# MCU.net
KiCad netlist of a schematic drawn in Altium Designer
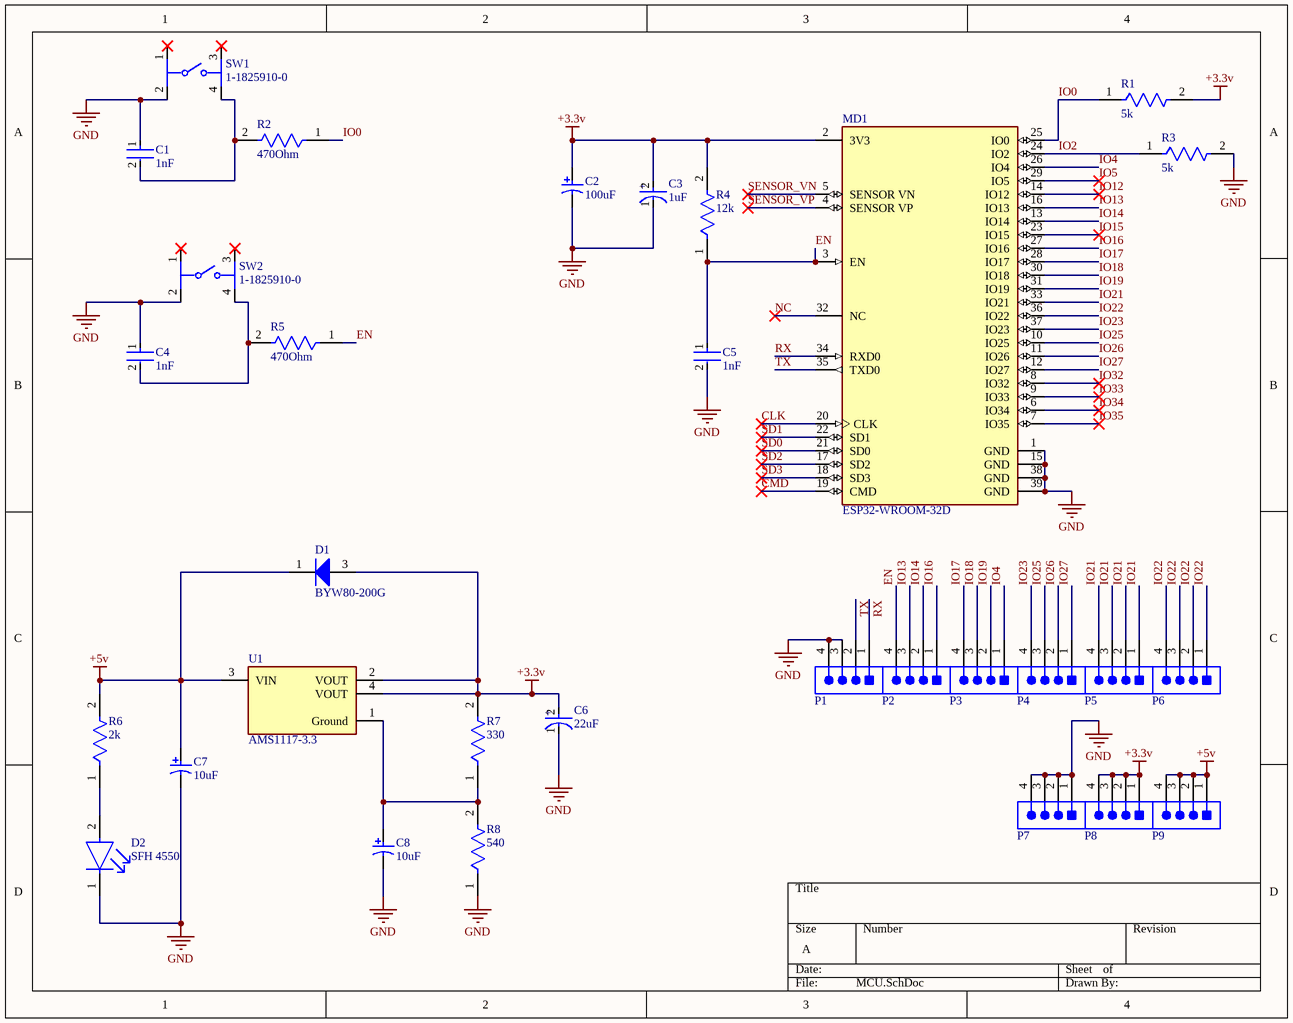
[diagram p0: MCU.SchDoc]

(export (version "E")
  (design (tool "Eeschema 10.0.6"))
  (components
    (comp (ref "C1")
      (value "1nF")
      (footprint "FP-VY2102M29Y5US6TV7-MFG")
      (fields (field (name "VOLTAGE") "300V") (field (name "TOLERANCE") "20%"))
      (libsource (lib "Altium Content Vault") (part "11868f565c42a9108669ba33697ecf6"))
    )
    (comp (ref "C2")
      (value "100uF")
      (footprint "NIC-RNS-8x11.5-2_V")
      (description "Aluminum Electrolytic Capacitor, 100 uF +/-20%, 10 V, -55 to 105 degC, 2-Pin THD, RoHS")
      (fields (field (name "PARTNUMBER") "RNS1A101MDN1KX") (field (name "MANUFACTURER") "Nichicon"))
      (libsource (lib "Altium Content Vault") (part "NIC-CAP-P-2"))
    )
    (comp (ref "C3")
      (value "1uF")
      (footprint "FP-ECA-2WHG010-MFG")
      (description "ECA-2WHG010 Aluminum Electrolytic Capacitor, 1 uF, 450 V, ± 20%, 2000 hours @ 105°C, Radial Leaded")
      (fields (field (name "TOLERANCE") "20%") (field (name "VOLTAGE") "450V"))
      (libsource (lib "Altium Content Vault") (part "a00bbbee19879c290e62620ae7e47b1"))
    )
    (comp (ref "C4")
      (value "1nF")
      (footprint "FP-VY2102M29Y5US6TV7-MFG")
      (fields (field (name "VOLTAGE") "300V") (field (name "TOLERANCE") "20%"))
      (libsource (lib "Altium Content Vault") (part "11868f565c42a9108669ba33697ecf6"))
    )
    (comp (ref "C5")
      (value "1nF")
      (footprint "FP-VY2102M29Y5US6TV7-MFG")
      (fields (field (name "VOLTAGE") "300V") (field (name "TOLERANCE") "20%"))
      (libsource (lib "Altium Content Vault") (part "11868f565c42a9108669ba33697ecf6"))
    )
    (comp (ref "C6")
      (value "22uF")
      (footprint "FP-RAD-TH-D_16_0_5-L_20_2-MFG")
      (description "Aluminum Electrolytic Capacitors (Radial Lead Type) 22uF ±20% 450V")
      (fields (field (name "TOLERANCE") "20%") (field (name "VOLTAGE") "450V"))
      (libsource (lib "Altium Content Vault") (part "203bc49f2ac43e59fd269a8c329ed05"))
    )
    (comp (ref "C7")
      (value "10uF")
      (footprint "NIC-RNS-8x11.5-2_V")
      (description "Aluminum Electrolytic Capacitor, 100 uF +/-20%, 10 V, -55 to 105 degC, 2-Pin THD, RoHS")
      (fields (field (name "PARTNUMBER") "RNS1A101MDN1KX") (field (name "MANUFACTURER") "Nichicon"))
      (libsource (lib "Altium Content Vault") (part "NIC-CAP-P-2"))
    )
    (comp (ref "C8")
      (value "10uF")
      (footprint "NIC-RNS-8x11.5-2_V")
      (description "Aluminum Electrolytic Capacitor, 100 uF +/-20%, 10 V, -55 to 105 degC, 2-Pin THD, RoHS")
      (fields (field (name "PARTNUMBER") "RNS1A101MDN1KX") (field (name "MANUFACTURER") "Nichicon"))
      (libsource (lib "Altium Content Vault") (part "NIC-CAP-P-2"))
    )
    (comp (ref "D1")
      (value "BYW80-200G")
      (footprint "ONSC-TO-220-2-221B-04_E")
      (description "SWITCHMODE(TM) Power Rectifier, 2-Pin TO-220, Pb-Free, Tube")
      (fields (field (name "MANUFACTURER") "On Semiconductor"))
      (libsource (lib "Altium Content Vault") (part "ONSC-D-K1A3-2_A"))
    )
    (comp (ref "D2")
      (value "SFH 4550")
      (footprint "FP-SFH_4550-MFG")
      (description "EMITTER IR 860NM 100MA RADIAL")
      (fields
        (field (name "OCTOPART") "https://octopart.com/sfh+4550-osram+opto-55410894")
        (field (name "MANUFACTURER") "Osram Opto")
      )
      (libsource (lib "Altium Content Vault") (part "75a0115997dd6a71327e26aab64f6f8"))
    )
    (comp (ref "MD1")
      (value "ESP32-WROOM-32D")
      (footprint "FP-ESP32-WROOM-32D-MFG")
      (description "WIFI MODULE 32MBITS SPI FLASH")
      (fields
        (field (name "OCTOPART") "https://octopart.com/esp32-wroom-32d-espressif+systems-91040050")
        (field (name "MANUFACTURER") "Espressif Systems")
      )
      (libsource (lib "Altium Content Vault") (part "a031a76f8c27026a7a7f4657ff233a3"))
    )
    (comp (ref "P1")
      (value "B4B-EH-A(LF)(SN)")
      (footprint "JST-B4B-EH-A_V")
      (fields (field (name "MANUFACTURER") "JST"))
      (libsource (lib "Altium Content Vault") (part "CN-1P-M-R4"))
    )
    (comp (ref "P2")
      (value "B4B-EH-A(LF)(SN)")
      (footprint "JST-B4B-EH-A_V")
      (fields (field (name "MANUFACTURER") "JST"))
      (libsource (lib "Altium Content Vault") (part "CN-1P-M-R4"))
    )
    (comp (ref "P3")
      (value "B4B-EH-A(LF)(SN)")
      (footprint "JST-B4B-EH-A_V")
      (fields (field (name "MANUFACTURER") "JST"))
      (libsource (lib "Altium Content Vault") (part "CN-1P-M-R4"))
    )
    (comp (ref "P4")
      (value "B4B-EH-A(LF)(SN)")
      (footprint "JST-B4B-EH-A_V")
      (fields (field (name "MANUFACTURER") "JST"))
      (libsource (lib "Altium Content Vault") (part "CN-1P-M-R4"))
    )
    (comp (ref "P5")
      (value "B4B-EH-A(LF)(SN)")
      (footprint "JST-B4B-EH-A_V")
      (fields (field (name "MANUFACTURER") "JST"))
      (libsource (lib "Altium Content Vault") (part "CN-1P-M-R4"))
    )
    (comp (ref "P6")
      (value "B4B-EH-A(LF)(SN)")
      (footprint "JST-B4B-EH-A_V")
      (fields (field (name "MANUFACTURER") "JST"))
      (libsource (lib "Altium Content Vault") (part "CN-1P-M-R4"))
    )
    (comp (ref "P7")
      (value "B4B-EH-A(LF)(SN)")
      (footprint "JST-B4B-EH-A_V")
      (fields (field (name "MANUFACTURER") "JST"))
      (libsource (lib "Altium Content Vault") (part "CN-1P-M-R4"))
    )
    (comp (ref "P8")
      (value "B4B-EH-A(LF)(SN)")
      (footprint "JST-B4B-EH-A_V")
      (fields (field (name "MANUFACTURER") "JST"))
      (libsource (lib "Altium Content Vault") (part "CN-1P-M-R4"))
    )
    (comp (ref "P9")
      (value "B4B-EH-A(LF)(SN)")
      (footprint "JST-B4B-EH-A_V")
      (fields (field (name "MANUFACTURER") "JST"))
      (libsource (lib "Altium Content Vault") (part "CN-1P-M-R4"))
    )
    (comp (ref "R1")
      (value "5k")
      (footprint "FP-MRS1600-MFG")
      (description "RES 20K OHM 0.4W 1% AXIAL")
      (fields (field (name "TOLERANCE") "1%"))
      (libsource (lib "Altium Content Vault") (part "1029c3af85768c4190bb7ad29bc67b5"))
    )
    (comp (ref "R2")
      (value "470Ohm")
      (footprint "FP-MRS1600-MFG")
      (description "RES 20K OHM 0.4W 1% AXIAL")
      (fields (field (name "TOLERANCE") "1%"))
      (libsource (lib "Altium Content Vault") (part "1029c3af85768c4190bb7ad29bc67b5"))
    )
    (comp (ref "R3")
      (value "5k")
      (footprint "FP-MRS1600-MFG")
      (description "RES 20K OHM 0.4W 1% AXIAL")
      (fields (field (name "TOLERANCE") "1%"))
      (libsource (lib "Altium Content Vault") (part "1029c3af85768c4190bb7ad29bc67b5"))
    )
    (comp (ref "R4")
      (value "12k")
      (footprint "FP-MRS1600-MFG")
      (description "RES 20K OHM 0.4W 1% AXIAL")
      (fields (field (name "TOLERANCE") "1%"))
      (libsource (lib "Altium Content Vault") (part "1029c3af85768c4190bb7ad29bc67b5"))
    )
    (comp (ref "R5")
      (value "470Ohm")
      (footprint "FP-MRS1600-MFG")
      (description "RES 20K OHM 0.4W 1% AXIAL")
      (fields (field (name "TOLERANCE") "1%"))
      (libsource (lib "Altium Content Vault") (part "1029c3af85768c4190bb7ad29bc67b5"))
    )
    (comp (ref "R6")
      (value "2k")
      (footprint "FP-MRS1600-MFG")
      (description "RES 20K OHM 0.4W 1% AXIAL")
      (fields (field (name "TOLERANCE") "1%"))
      (libsource (lib "Altium Content Vault") (part "1029c3af85768c4190bb7ad29bc67b5"))
    )
    (comp (ref "R7")
      (value "330")
      (footprint "FP-MRS1600-MFG")
      (description "RES 20K OHM 0.4W 1% AXIAL")
      (fields (field (name "TOLERANCE") "1%"))
      (libsource (lib "Altium Content Vault") (part "1029c3af85768c4190bb7ad29bc67b5"))
    )
    (comp (ref "R8")
      (value "540")
      (footprint "FP-MRS1600-MFG")
      (description "RES 20K OHM 0.4W 1% AXIAL")
      (fields (field (name "TOLERANCE") "1%"))
      (libsource (lib "Altium Content Vault") (part "1029c3af85768c4190bb7ad29bc67b5"))
    )
    (comp (ref "SW1")
      (value "1-1825910-0")
      (footprint "FP-1-1825910-0-MFG")
      (description "SWITCH TACTILE SPST-NO 0.05A 24V")
      (libsource (lib "Altium Content Vault") (part "b8895f3f4cefb76e1819d2863dba89b"))
    )
    (comp (ref "SW2")
      (value "1-1825910-0")
      (footprint "FP-1-1825910-0-MFG")
      (description "SWITCH TACTILE SPST-NO 0.05A 24V")
      (libsource (lib "Altium Content Vault") (part "b8895f3f4cefb76e1819d2863dba89b"))
    )
    (comp (ref "U1")
      (value "AMS1117-3.3")
      (footprint "FP-AMS1117-IPC_C")
      (description "LDO Voltage Regulators 1A, 3.3V")
      (fields
        (field (name "OCTOPART") "https://octopart.com/ams1117-3.3-advanced+monolithic+systems-25899300")
        (field (name "MANUFACTURER") "Advanced Monolithic Systems")
      )
      (libsource (lib "Altium Content Vault") (part "8bdbb5f8e77002000e30dd2845d0354"))
    )
  )
  (nets
    (net (code "1") (name "+3.3v") (class "Default")
      (node (ref "C2") (pin "1") (pinfunction "1_1") (pintype "passive"))
      (node (ref "C3") (pin "2") (pinfunction "A_2") (pintype "passive"))
      (node (ref "C6") (pin "2") (pinfunction "A_2") (pintype "passive"))
      (node (ref "D1") (pin "3") (pinfunction "A_3") (pintype "passive"))
      (node (ref "MD1") (pin "2") (pinfunction "3V3_2") (pintype "power_in"))
      (node (ref "P8") (pin "1") (pinfunction "1_1") (pintype "passive"))
      (node (ref "P8") (pin "2") (pinfunction "2_2") (pintype "passive"))
      (node (ref "P8") (pin "3") (pinfunction "3_3") (pintype "passive"))
      (node (ref "P8") (pin "4") (pinfunction "4_4") (pintype "passive"))
      (node (ref "R1") (pin "2") (pinfunction "2_2") (pintype "passive"))
      (node (ref "R4") (pin "2") (pinfunction "2_2") (pintype "passive"))
      (node (ref "R7") (pin "2") (pinfunction "2_2") (pintype "passive"))
      (node (ref "U1") (pin "2") (pinfunction "VOUT_2") (pintype "passive"))
      (node (ref "U1") (pin "4") (pinfunction "VOUT_4") (pintype "passive"))
    )
    (net (code "2") (name "+5v") (class "Default")
      (node (ref "C7") (pin "1") (pinfunction "1_1") (pintype "passive"))
      (node (ref "D1") (pin "1") (pinfunction "K_1") (pintype "passive"))
      (node (ref "P9") (pin "1") (pinfunction "1_1") (pintype "passive"))
      (node (ref "P9") (pin "2") (pinfunction "2_2") (pintype "passive"))
      (node (ref "P9") (pin "3") (pinfunction "3_3") (pintype "passive"))
      (node (ref "P9") (pin "4") (pinfunction "4_4") (pintype "passive"))
      (node (ref "R6") (pin "2") (pinfunction "2_2") (pintype "passive"))
      (node (ref "U1") (pin "3") (pinfunction "VIN_3") (pintype "power_in"))
    )
    (net (code "4") (name "/CLK") (class "Default")
      (node (ref "MD1") (pin "20") (pinfunction "CLK_20") (pintype "input+no_connect"))
    )
    (net (code "5") (name "/CMD") (class "Default")
      (node (ref "MD1") (pin "19") (pinfunction "CMD_19") (pintype "bidirectional+no_connect"))
    )
    (net (code "6") (name "/EN") (class "Default")
      (node (ref "C5") (pin "1") (pinfunction "1_1") (pintype "passive"))
      (node (ref "MD1") (pin "3") (pinfunction "EN_3") (pintype "input"))
      (node (ref "P2") (pin "4") (pinfunction "4_4") (pintype "passive"))
      (node (ref "R4") (pin "1") (pinfunction "1_1") (pintype "passive"))
      (node (ref "R5") (pin "1") (pinfunction "1_1") (pintype "passive"))
    )
    (net (code "7") (name "/IO0") (class "Default")
      (node (ref "MD1") (pin "25") (pinfunction "IO0_25") (pintype "bidirectional"))
      (node (ref "R1") (pin "1") (pinfunction "1_1") (pintype "passive"))
      (node (ref "R2") (pin "1") (pinfunction "1_1") (pintype "passive"))
    )
    (net (code "8") (name "/IO2") (class "Default")
      (node (ref "MD1") (pin "24") (pinfunction "IO2_24") (pintype "bidirectional"))
      (node (ref "R3") (pin "1") (pinfunction "1_1") (pintype "passive"))
    )
    (net (code "9") (name "/IO4") (class "Default")
      (node (ref "MD1") (pin "26") (pinfunction "IO4_26") (pintype "bidirectional"))
      (node (ref "P3") (pin "1") (pinfunction "1_1") (pintype "passive"))
    )
    (net (code "10") (name "/IO5") (class "Default")
      (node (ref "MD1") (pin "29") (pinfunction "IO5_29") (pintype "bidirectional+no_connect"))
    )
    (net (code "11") (name "/IO12") (class "Default")
      (node (ref "MD1") (pin "14") (pinfunction "IO12_14") (pintype "bidirectional+no_connect"))
    )
    (net (code "12") (name "/IO13") (class "Default")
      (node (ref "MD1") (pin "16") (pinfunction "IO13_16") (pintype "bidirectional"))
      (node (ref "P2") (pin "3") (pinfunction "3_3") (pintype "passive"))
    )
    (net (code "13") (name "/IO14") (class "Default")
      (node (ref "MD1") (pin "13") (pinfunction "IO14_13") (pintype "bidirectional"))
      (node (ref "P2") (pin "2") (pinfunction "2_2") (pintype "passive"))
    )
    (net (code "14") (name "/IO15") (class "Default")
      (node (ref "MD1") (pin "23") (pinfunction "IO15_23") (pintype "bidirectional+no_connect"))
    )
    (net (code "15") (name "/IO16") (class "Default")
      (node (ref "MD1") (pin "27") (pinfunction "IO16_27") (pintype "bidirectional"))
      (node (ref "P2") (pin "1") (pinfunction "1_1") (pintype "passive"))
    )
    (net (code "16") (name "/IO17") (class "Default")
      (node (ref "MD1") (pin "28") (pinfunction "IO17_28") (pintype "bidirectional"))
      (node (ref "P3") (pin "4") (pinfunction "4_4") (pintype "passive"))
    )
    (net (code "17") (name "/IO18") (class "Default")
      (node (ref "MD1") (pin "30") (pinfunction "IO18_30") (pintype "bidirectional"))
      (node (ref "P3") (pin "3") (pinfunction "3_3") (pintype "passive"))
    )
    (net (code "18") (name "/IO19") (class "Default")
      (node (ref "MD1") (pin "31") (pinfunction "IO19_31") (pintype "bidirectional"))
      (node (ref "P3") (pin "2") (pinfunction "2_2") (pintype "passive"))
    )
    (net (code "19") (name "/IO21") (class "Default")
      (node (ref "MD1") (pin "33") (pinfunction "IO21_33") (pintype "bidirectional"))
      (node (ref "P5") (pin "1") (pinfunction "1_1") (pintype "passive"))
      (node (ref "P5") (pin "2") (pinfunction "2_2") (pintype "passive"))
      (node (ref "P5") (pin "3") (pinfunction "3_3") (pintype "passive"))
      (node (ref "P5") (pin "4") (pinfunction "4_4") (pintype "passive"))
    )
    (net (code "20") (name "/IO22") (class "Default")
      (node (ref "MD1") (pin "36") (pinfunction "IO22_36") (pintype "bidirectional"))
      (node (ref "P6") (pin "1") (pinfunction "1_1") (pintype "passive"))
      (node (ref "P6") (pin "2") (pinfunction "2_2") (pintype "passive"))
      (node (ref "P6") (pin "3") (pinfunction "3_3") (pintype "passive"))
      (node (ref "P6") (pin "4") (pinfunction "4_4") (pintype "passive"))
    )
    (net (code "21") (name "/IO23") (class "Default")
      (node (ref "MD1") (pin "37") (pinfunction "IO23_37") (pintype "bidirectional"))
      (node (ref "P4") (pin "4") (pinfunction "4_4") (pintype "passive"))
    )
    (net (code "22") (name "/IO25") (class "Default")
      (node (ref "MD1") (pin "10") (pinfunction "IO25_10") (pintype "bidirectional"))
      (node (ref "P4") (pin "3") (pinfunction "3_3") (pintype "passive"))
    )
    (net (code "23") (name "/IO26") (class "Default")
      (node (ref "MD1") (pin "11") (pinfunction "IO26_11") (pintype "bidirectional"))
      (node (ref "P4") (pin "2") (pinfunction "2_2") (pintype "passive"))
    )
    (net (code "24") (name "/IO27") (class "Default")
      (node (ref "MD1") (pin "12") (pinfunction "IO27_12") (pintype "bidirectional"))
      (node (ref "P4") (pin "1") (pinfunction "1_1") (pintype "passive"))
    )
    (net (code "25") (name "/IO32") (class "Default")
      (node (ref "MD1") (pin "8") (pinfunction "IO32_8") (pintype "bidirectional+no_connect"))
    )
    (net (code "26") (name "/IO33") (class "Default")
      (node (ref "MD1") (pin "9") (pinfunction "IO33_9") (pintype "bidirectional+no_connect"))
    )
    (net (code "27") (name "/IO34") (class "Default")
      (node (ref "MD1") (pin "6") (pinfunction "IO34_6") (pintype "bidirectional+no_connect"))
    )
    (net (code "28") (name "/IO35") (class "Default")
      (node (ref "MD1") (pin "7") (pinfunction "IO35_7") (pintype "bidirectional+no_connect"))
    )
    (net (code "29") (name "/NC") (class "Default")
      (node (ref "MD1") (pin "32") (pinfunction "NC_32") (pintype "passive+no_connect"))
    )
    (net (code "30") (name "/RX") (class "Default")
      (node (ref "MD1") (pin "34") (pinfunction "RXD0_34") (pintype "input"))
      (node (ref "P1") (pin "1") (pinfunction "1_1") (pintype "passive"))
    )
    (net (code "31") (name "/SD0") (class "Default")
      (node (ref "MD1") (pin "21") (pinfunction "SD0_21") (pintype "bidirectional+no_connect"))
    )
    (net (code "32") (name "/SD1") (class "Default")
      (node (ref "MD1") (pin "22") (pinfunction "SD1_22") (pintype "bidirectional+no_connect"))
    )
    (net (code "33") (name "/SD2") (class "Default")
      (node (ref "MD1") (pin "17") (pinfunction "SD2_17") (pintype "bidirectional+no_connect"))
    )
    (net (code "34") (name "/SD3") (class "Default")
      (node (ref "MD1") (pin "18") (pinfunction "SD3_18") (pintype "bidirectional+no_connect"))
    )
    (net (code "35") (name "/SENSOR_VN") (class "Default")
      (node (ref "MD1") (pin "5") (pinfunction "SENSOR_VN_5") (pintype "bidirectional+no_connect"))
    )
    (net (code "36") (name "/SENSOR_VP") (class "Default")
      (node (ref "MD1") (pin "4") (pinfunction "SENSOR_VP_4") (pintype "bidirectional+no_connect"))
    )
    (net (code "37") (name "/TX") (class "Default")
      (node (ref "MD1") (pin "35") (pinfunction "TXD0_35") (pintype "output"))
      (node (ref "P1") (pin "2") (pinfunction "2_2") (pintype "passive"))
    )
    (net (code "38") (name "GND") (class "Default")
      (node (ref "C1") (pin "1") (pinfunction "1_1") (pintype "passive"))
      (node (ref "C2") (pin "2") (pinfunction "2_2") (pintype "passive"))
      (node (ref "C3") (pin "1") (pinfunction "C_1") (pintype "passive"))
      (node (ref "C4") (pin "1") (pinfunction "1_1") (pintype "passive"))
      (node (ref "C5") (pin "2") (pinfunction "2_2") (pintype "passive"))
      (node (ref "C6") (pin "1") (pinfunction "C_1") (pintype "passive"))
      (node (ref "C7") (pin "2") (pinfunction "2_2") (pintype "passive"))
      (node (ref "C8") (pin "2") (pinfunction "2_2") (pintype "passive"))
      (node (ref "D2") (pin "1") (pinfunction "C_1") (pintype "passive"))
      (node (ref "MD1") (pin "1") (pinfunction "GND_1") (pintype "power_in"))
      (node (ref "MD1") (pin "15") (pinfunction "GND_15") (pintype "power_in"))
      (node (ref "MD1") (pin "38") (pinfunction "GND_38") (pintype "power_in"))
      (node (ref "MD1") (pin "39") (pinfunction "GND_39") (pintype "power_in"))
      (node (ref "P1") (pin "3") (pinfunction "3_3") (pintype "passive"))
      (node (ref "P1") (pin "4") (pinfunction "4_4") (pintype "passive"))
      (node (ref "P7") (pin "1") (pinfunction "1_1") (pintype "passive"))
      (node (ref "P7") (pin "2") (pinfunction "2_2") (pintype "passive"))
      (node (ref "P7") (pin "3") (pinfunction "3_3") (pintype "passive"))
      (node (ref "P7") (pin "4") (pinfunction "4_4") (pintype "passive"))
      (node (ref "R3") (pin "2") (pinfunction "2_2") (pintype "passive"))
      (node (ref "R8") (pin "1") (pinfunction "1_1") (pintype "passive"))
      (node (ref "SW1") (pin "2") (pinfunction "2_2") (pintype "passive"))
      (node (ref "SW2") (pin "2") (pinfunction "2_2") (pintype "passive"))
    )
    (net (code "39") (name "Net-(C1-Pad2)") (class "Default")
      (node (ref "C1") (pin "2") (pinfunction "2_2") (pintype "passive"))
      (node (ref "R2") (pin "2") (pinfunction "2_2") (pintype "passive"))
      (node (ref "SW1") (pin "4") (pinfunction "4_4") (pintype "passive"))
    )
    (net (code "40") (name "Net-(C4-Pad2)") (class "Default")
      (node (ref "C4") (pin "2") (pinfunction "2_2") (pintype "passive"))
      (node (ref "R5") (pin "2") (pinfunction "2_2") (pintype "passive"))
      (node (ref "SW2") (pin "4") (pinfunction "4_4") (pintype "passive"))
    )
    (net (code "41") (name "Net-(D2-A)") (class "Default")
      (node (ref "D2") (pin "2") (pinfunction "A_2") (pintype "passive"))
      (node (ref "R6") (pin "1") (pinfunction "1_1") (pintype "passive"))
    )
    (net (code "42") (name "Net-(U1-Ground)") (class "Default")
      (node (ref "C8") (pin "1") (pinfunction "1_1") (pintype "passive"))
      (node (ref "R7") (pin "1") (pinfunction "1_1") (pintype "passive"))
      (node (ref "R8") (pin "2") (pinfunction "2_2") (pintype "passive"))
      (node (ref "U1") (pin "1") (pinfunction "Ground_1") (pintype "power_in"))
    )
    (net (code "43") (name "unconnected-(SW1-Pad1)") (class "Default")
      (node (ref "SW1") (pin "1") (pinfunction "1_1") (pintype "passive+no_connect"))
    )
    (net (code "44") (name "unconnected-(SW1-Pad3)") (class "Default")
      (node (ref "SW1") (pin "3") (pinfunction "3_3") (pintype "passive+no_connect"))
    )
    (net (code "45") (name "unconnected-(SW2-Pad1)") (class "Default")
      (node (ref "SW2") (pin "1") (pinfunction "1_1") (pintype "passive+no_connect"))
    )
    (net (code "46") (name "unconnected-(SW2-Pad3)") (class "Default")
      (node (ref "SW2") (pin "3") (pinfunction "3_3") (pintype "passive+no_connect"))
    )
  )
)
